# gcsc_ii.net
KiCad netlist of a schematic drawn in EAGLE
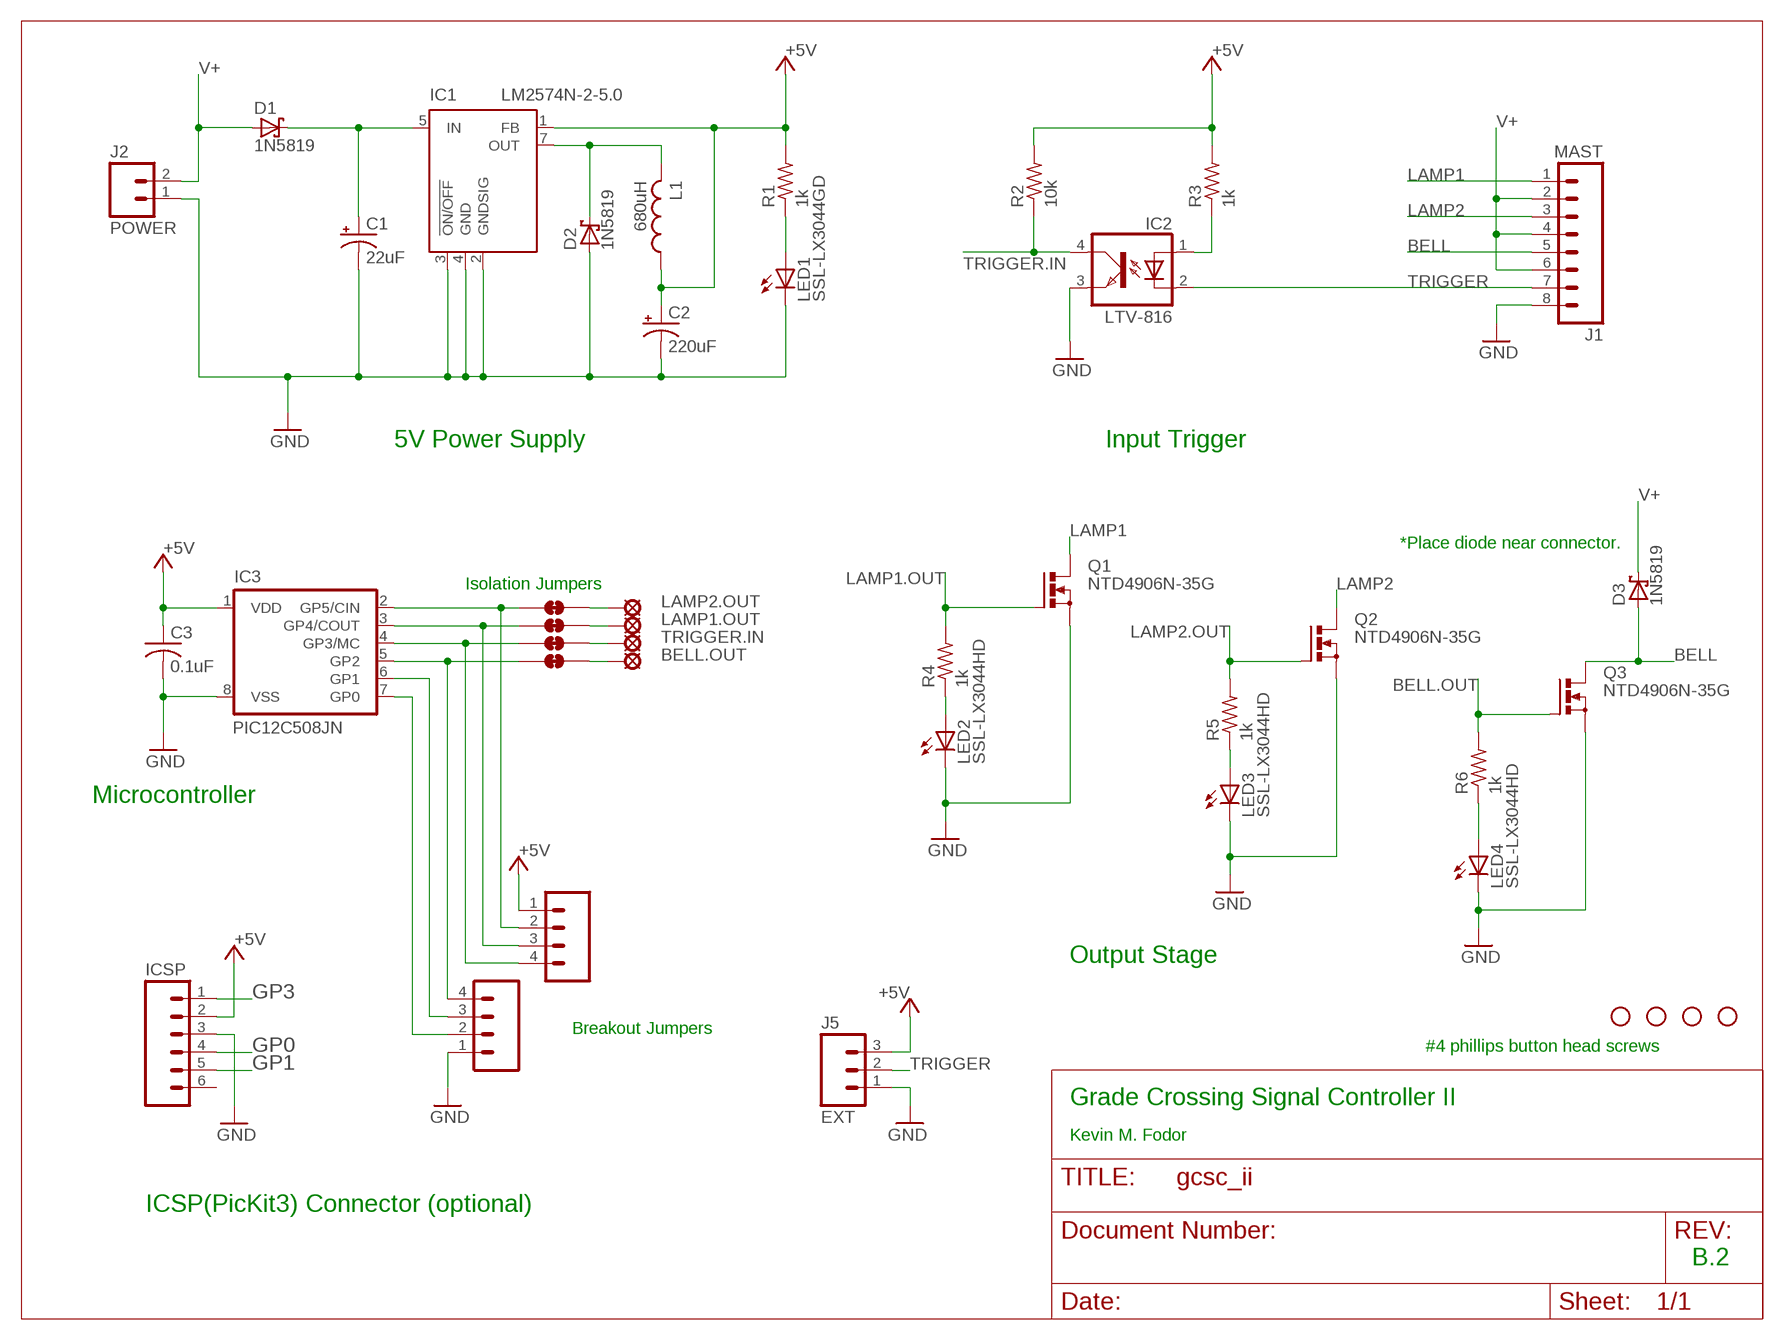
[diagram p0: schematic, sheet 1]

(export (version "E")
  (design (tool "Eeschema 10.0.6"))
  (components
    (comp (ref "BELL.OUT")
      (value "BELL")
      (footprint "eagle-import:LSP10")
      (fields (field (name "PARTNO") "22-28-4012"))
      (libsource (lib "eagle-import") (part "LSP10"))
    )
    (comp (ref "C1")
      (value "22uF")
      (footprint "eagle-import:E2-5")
      (fields (field (name "PARTNO") "EEU-FR1H220"))
      (libsource (lib "eagle-import") (part "CPOL-USFR-5"))
    )
    (comp (ref "C2")
      (value "220uF")
      (footprint "eagle-import:E2,5-6,3")
      (fields (field (name "PARTNO") "EEU-FR1C221"))
      (libsource (lib "eagle-import") (part "CPOL-USFR-6,3"))
    )
    (comp (ref "C3")
      (value "0.1uF")
      (footprint "eagle-import:C025-024X044")
      (fields (field (name "PARTNO") "21RZ310-RC"))
      (libsource (lib "eagle-import") (part "C-USC025-024X044"))
    )
    (comp (ref "D1")
      (value "1N5819")
      (footprint "eagle-import:DO41-10")
      (libsource (lib "eagle-import") (part "SCHOTTKY-DIODEDO41"))
    )
    (comp (ref "D2")
      (value "1N5819")
      (footprint "eagle-import:DO41-10")
      (libsource (lib "eagle-import") (part "SCHOTTKY-DIODEDO41"))
    )
    (comp (ref "D3")
      (value "1N5819")
      (footprint "eagle-import:DO41-10")
      (libsource (lib "eagle-import") (part "SCHOTTKY-DIODEDO41"))
    )
    (comp (ref "GP2")
      (value "GP2")
      (footprint "eagle-import:SJ_2S-TRACE")
      (libsource (lib "eagle-import") (part "SJ_CLOSED"))
    )
    (comp (ref "GP3")
      (value "GP3")
      (footprint "eagle-import:SJ_2S-TRACE")
      (libsource (lib "eagle-import") (part "SJ_CLOSED"))
    )
    (comp (ref "GP4")
      (value "GP4")
      (footprint "eagle-import:SJ_2S-TRACE")
      (libsource (lib "eagle-import") (part "SJ_CLOSED"))
    )
    (comp (ref "GP5")
      (value "GP5")
      (footprint "eagle-import:SJ_2S-TRACE")
      (libsource (lib "eagle-import") (part "SJ_CLOSED"))
    )
    (comp (ref "IC1")
      (value "LM2574N-2-5.0")
      (footprint "eagle-import:DIL8")
      (fields (field (name "PARTNO") "LM2574N-5G"))
      (libsource (lib "eagle-import") (part "LM2574?-N-25.0"))
    )
    (comp (ref "IC2")
      (value "LTV-816")
      (footprint "eagle-import:DIL04")
      (libsource (lib "eagle-import") (part "LTV816"))
    )
    (comp (ref "IC3")
      (value "PIC12C508JN")
      (footprint "eagle-import:DIL8")
      (fields
        (field (name "MF") "MICROCHIP")
        (field (name "MPN") "PIC12C508-04/P")
        (field (name "MPN_1") "PIC12C508-04/P")
        (field (name "OC_FARNELL") "9758771")
        (field (name "OC_NEWARK") "60K6710")
        (field (name "PARTNO") "PIC12F508-I/P")
      )
      (libsource (lib "eagle-import") (part "PIC12C?JN508"))
    )
    (comp (ref "ICSP")
      (value "PIC_ICSP_RA")
      (footprint "eagle-import:PIC_ICSP")
      (fields (field (name "PARTNO") "68016-106HLF"))
      (libsource (lib "eagle-import") (part "PIC_ICSP_RA"))
    )
    (comp (ref "J1")
      (value "MAST")
      (footprint "eagle-import:KK-156-8-RA")
      (fields (field (name "PARTNO") "26-60-5080"))
      (libsource (lib "eagle-import") (part "KK-156-8-RA"))
    )
    (comp (ref "J2")
      (value "POWER")
      (footprint "eagle-import:KK-156-2-RA")
      (fields (field (name "PARTNO") "26-60-5020"))
      (libsource (lib "eagle-import") (part "KK-156-2RA"))
    )
    (comp (ref "J3")
      (value "IC3_1-4")
      (footprint "eagle-import:1X04_LOCK")
      (fields (field (name "PARTNO") "22-28-4042"))
      (libsource (lib "eagle-import") (part "M04LOCK"))
    )
    (comp (ref "J4")
      (value "IC3_5-8")
      (footprint "eagle-import:1X04_LOCK")
      (fields (field (name "PARTNO") "22-28-4042"))
      (libsource (lib "eagle-import") (part "M04LOCK"))
    )
    (comp (ref "J5")
      (value "EXT")
      (footprint "eagle-import:MOLEX-1X3_LOCK")
      (fields (field (name "PARTNO") "22-27-2031"))
      (libsource (lib "eagle-import") (part "M03POLAR_LOCK"))
    )
    (comp (ref "L1")
      (value "680uH")
      (footprint "eagle-import:RLB0608")
      (fields (field (name "PARTNO") "RLB0608-681KL"))
      (libsource (lib "eagle-import") (part "RLB0608"))
    )
    (comp (ref "LAMP1.OUT")
      (value "LAMP1")
      (footprint "eagle-import:LSP10")
      (fields (field (name "PARTNO") "22-28-4012"))
      (libsource (lib "eagle-import") (part "LSP10"))
    )
    (comp (ref "LAMP2.OUT")
      (value "LAMP2")
      (footprint "eagle-import:LSP10")
      (fields (field (name "PARTNO") "22-28-4012"))
      (libsource (lib "eagle-import") (part "LSP10"))
    )
    (comp (ref "LED1")
      (value "SSL-LX3044GD")
      (footprint "eagle-import:LED3MM")
      (libsource (lib "eagle-import") (part "LED3MM"))
    )
    (comp (ref "LED2")
      (value "SSL-LX3044HD")
      (footprint "eagle-import:LED3MM")
      (libsource (lib "eagle-import") (part "LED3MM"))
    )
    (comp (ref "LED3")
      (value "SSL-LX3044HD")
      (footprint "eagle-import:LED3MM")
      (libsource (lib "eagle-import") (part "LED3MM"))
    )
    (comp (ref "LED4")
      (value "SSL-LX3044HD")
      (footprint "eagle-import:LED3MM")
      (libsource (lib "eagle-import") (part "LED3MM"))
    )
    (comp (ref "Q1")
      (value "NTD4906N-35G")
      (footprint "eagle-import:I-PAK_STRAIGHT_LEAD")
      (libsource (lib "eagle-import") (part "NTD4906N"))
    )
    (comp (ref "Q2")
      (value "NTD4906N-35G")
      (footprint "eagle-import:I-PAK_STRAIGHT_LEAD")
      (libsource (lib "eagle-import") (part "NTD4906N"))
    )
    (comp (ref "Q3")
      (value "NTD4906N-35G")
      (footprint "eagle-import:I-PAK_STRAIGHT_LEAD")
      (libsource (lib "eagle-import") (part "NTD4906N"))
    )
    (comp (ref "R1")
      (value "1k")
      (footprint "eagle-import:0207_10")
      (fields (field (name "PARTNO") "299-1K-RC"))
      (libsource (lib "eagle-import") (part "R-US0207/10"))
    )
    (comp (ref "R2")
      (value "10k")
      (footprint "eagle-import:0207_10")
      (fields (field (name "PARTNO") "299-10K-RC"))
      (libsource (lib "eagle-import") (part "R-US0207/10"))
    )
    (comp (ref "R3")
      (value "1k")
      (footprint "eagle-import:0207_10")
      (fields (field (name "PARTNO") "299-1K-RC"))
      (libsource (lib "eagle-import") (part "R-US0207/10"))
    )
    (comp (ref "R4")
      (value "1k")
      (footprint "eagle-import:0207_10")
      (fields (field (name "PARTNO") "299-1K-RC"))
      (libsource (lib "eagle-import") (part "R-US0207/10"))
    )
    (comp (ref "R5")
      (value "1k")
      (footprint "eagle-import:0207_10")
      (fields (field (name "PARTNO") "299-1K-RC"))
      (libsource (lib "eagle-import") (part "R-US0207/10"))
    )
    (comp (ref "R6")
      (value "1k")
      (footprint "eagle-import:0207_10")
      (fields (field (name "PARTNO") "299-1K-RC"))
      (libsource (lib "eagle-import") (part "R-US0207/10"))
    )
    (comp (ref "TRIGGER.IN")
      (value "TRIGGER")
      (footprint "eagle-import:LSP10")
      (fields (field (name "PARTNO") "22-28-4012"))
      (libsource (lib "eagle-import") (part "LSP10"))
    )
    (comp (ref "U$1")
      (value "STAND-OFF")
      (footprint "eagle-import:STAND-OFF")
      (libsource (lib "eagle-import") (part "STAND-OFF"))
    )
    (comp (ref "U$2")
      (value "STAND-OFF")
      (footprint "eagle-import:STAND-OFF")
      (libsource (lib "eagle-import") (part "STAND-OFF"))
    )
    (comp (ref "U$3")
      (value "STAND-OFF")
      (footprint "eagle-import:STAND-OFF")
      (libsource (lib "eagle-import") (part "STAND-OFF"))
    )
    (comp (ref "U$4")
      (value "STAND-OFF")
      (footprint "eagle-import:STAND-OFF")
      (libsource (lib "eagle-import") (part "STAND-OFF"))
    )
  )
  (nets
    (net (code "1") (name "+5V") (class "Default")
      (node (ref "C2") (pin "+") (pinfunction "+_+") (pintype "passive"))
      (node (ref "C3") (pin "1") (pinfunction "1_1") (pintype "passive"))
      (node (ref "IC1") (pin "1") (pinfunction "FB_1") (pintype "input"))
      (node (ref "IC3") (pin "1") (pinfunction "VDD_1") (pintype "power_in"))
      (node (ref "ICSP") (pin "2") (pinfunction "VDD_2") (pintype "power_in"))
      (node (ref "J3") (pin "1") (pinfunction "1_1") (pintype "passive"))
      (node (ref "J5") (pin "3") (pinfunction "3_3") (pintype "passive"))
      (node (ref "L1") (pin "1") (pinfunction "1_1") (pintype "passive"))
      (node (ref "R1") (pin "2") (pinfunction "2_2") (pintype "passive"))
      (node (ref "R2") (pin "2") (pinfunction "2_2") (pintype "passive"))
      (node (ref "R3") (pin "2") (pinfunction "2_2") (pintype "passive"))
    )
    (net (code "2") (name "/BELL") (class "Default")
      (node (ref "D3") (pin "A") (pinfunction "A_A") (pintype "passive"))
      (node (ref "J1") (pin "5") (pinfunction "5_5") (pintype "passive"))
      (node (ref "Q3") (pin "2") (pinfunction "D_2") (pintype "passive"))
    )
    (net (code "3") (name "/BELL.OUT") (class "Default")
      (node (ref "BELL.OUT") (pin "MP") (pinfunction "MP_MP") (pintype "passive"))
      (node (ref "GP2") (pin "2") (pinfunction "2_2") (pintype "passive"))
      (node (ref "Q3") (pin "1") (pinfunction "G_1") (pintype "passive"))
      (node (ref "R6") (pin "2") (pinfunction "2_2") (pintype "passive"))
    )
    (net (code "4") (name "/GP0") (class "Default")
      (node (ref "IC3") (pin "7") (pinfunction "GP0_7") (pintype "bidirectional"))
      (node (ref "ICSP") (pin "4") (pinfunction "ICSPDAT_4") (pintype "passive"))
      (node (ref "J4") (pin "2") (pinfunction "2_2") (pintype "passive"))
    )
    (net (code "5") (name "/GP1") (class "Default")
      (node (ref "IC3") (pin "6") (pinfunction "GP1_6") (pintype "bidirectional"))
      (node (ref "ICSP") (pin "5") (pinfunction "ICSPCLK_5") (pintype "passive"))
      (node (ref "J4") (pin "3") (pinfunction "3_3") (pintype "passive"))
    )
    (net (code "6") (name "/GP3") (class "Default")
      (node (ref "GP3") (pin "1") (pinfunction "1_1") (pintype "passive"))
      (node (ref "IC3") (pin "4") (pinfunction "GP3/MC_4") (pintype "input"))
      (node (ref "ICSP") (pin "1") (pinfunction "~{MCLR}_1") (pintype "passive"))
      (node (ref "J3") (pin "4") (pinfunction "4_4") (pintype "passive"))
    )
    (net (code "7") (name "/LAMP1") (class "Default")
      (node (ref "J1") (pin "1") (pinfunction "1_1") (pintype "passive"))
      (node (ref "Q1") (pin "2") (pinfunction "D_2") (pintype "passive"))
    )
    (net (code "8") (name "/LAMP1.OUT") (class "Default")
      (node (ref "GP4") (pin "2") (pinfunction "2_2") (pintype "passive"))
      (node (ref "LAMP1.OUT") (pin "MP") (pinfunction "MP_MP") (pintype "passive"))
      (node (ref "Q1") (pin "1") (pinfunction "G_1") (pintype "passive"))
      (node (ref "R4") (pin "2") (pinfunction "2_2") (pintype "passive"))
    )
    (net (code "9") (name "/LAMP2") (class "Default")
      (node (ref "J1") (pin "3") (pinfunction "3_3") (pintype "passive"))
      (node (ref "Q2") (pin "2") (pinfunction "D_2") (pintype "passive"))
    )
    (net (code "10") (name "/LAMP2.OUT") (class "Default")
      (node (ref "GP5") (pin "2") (pinfunction "2_2") (pintype "passive"))
      (node (ref "LAMP2.OUT") (pin "MP") (pinfunction "MP_MP") (pintype "passive"))
      (node (ref "Q2") (pin "1") (pinfunction "G_1") (pintype "passive"))
      (node (ref "R5") (pin "2") (pinfunction "2_2") (pintype "passive"))
    )
    (net (code "11") (name "/TRIGGER") (class "Default")
      (node (ref "IC2") (pin "2") (pinfunction "C_2") (pintype "passive"))
      (node (ref "J1") (pin "7") (pinfunction "7_7") (pintype "passive"))
      (node (ref "J5") (pin "2") (pinfunction "2_2") (pintype "passive"))
    )
    (net (code "12") (name "/TRIGGER.IN") (class "Default")
      (node (ref "GP3") (pin "2") (pinfunction "2_2") (pintype "passive"))
      (node (ref "IC2") (pin "4") (pinfunction "COL_4") (pintype "passive"))
      (node (ref "R2") (pin "1") (pinfunction "1_1") (pintype "passive"))
      (node (ref "TRIGGER.IN") (pin "MP") (pinfunction "MP_MP") (pintype "passive"))
    )
    (net (code "13") (name "/V+") (class "Default")
      (node (ref "D1") (pin "A") (pinfunction "A_A") (pintype "passive"))
      (node (ref "D3") (pin "C") (pinfunction "C_C") (pintype "passive"))
      (node (ref "J1") (pin "2") (pinfunction "2_2") (pintype "passive"))
      (node (ref "J1") (pin "4") (pinfunction "4_4") (pintype "passive"))
      (node (ref "J1") (pin "6") (pinfunction "6_6") (pintype "passive"))
      (node (ref "J2") (pin "2") (pinfunction "2_2") (pintype "passive"))
    )
    (net (code "14") (name "GND") (class "Default")
      (node (ref "C1") (pin "-") (pinfunction "-_-") (pintype "passive"))
      (node (ref "C2") (pin "-") (pinfunction "-_-") (pintype "passive"))
      (node (ref "C3") (pin "2") (pinfunction "2_2") (pintype "passive"))
      (node (ref "D2") (pin "A") (pinfunction "A_A") (pintype "passive"))
      (node (ref "IC1") (pin "2") (pinfunction "GNDSIG_2") (pintype "input"))
      (node (ref "IC1") (pin "3") (pinfunction "~{ON/OFF}_3") (pintype "input"))
      (node (ref "IC1") (pin "4") (pinfunction "GND_4") (pintype "power_in"))
      (node (ref "IC2") (pin "3") (pinfunction "EMIT_3") (pintype "passive"))
      (node (ref "IC3") (pin "8") (pinfunction "VSS_8") (pintype "power_in"))
      (node (ref "ICSP") (pin "3") (pinfunction "VSS_3") (pintype "power_in"))
      (node (ref "J1") (pin "8") (pinfunction "8_8") (pintype "passive"))
      (node (ref "J2") (pin "1") (pinfunction "1_1") (pintype "passive"))
      (node (ref "J4") (pin "1") (pinfunction "1_1") (pintype "passive"))
      (node (ref "J5") (pin "1") (pinfunction "1_1") (pintype "passive"))
      (node (ref "LED1") (pin "K") (pinfunction "C_K") (pintype "passive"))
      (node (ref "LED2") (pin "K") (pinfunction "C_K") (pintype "passive"))
      (node (ref "LED3") (pin "K") (pinfunction "C_K") (pintype "passive"))
      (node (ref "LED4") (pin "K") (pinfunction "C_K") (pintype "passive"))
      (node (ref "Q1") (pin "3") (pinfunction "S_3") (pintype "passive"))
      (node (ref "Q2") (pin "3") (pinfunction "S_3") (pintype "passive"))
      (node (ref "Q3") (pin "3") (pinfunction "S_3") (pintype "passive"))
    )
    (net (code "15") (name "Net-(IC1-IN)") (class "Default")
      (node (ref "C1") (pin "+") (pinfunction "+_+") (pintype "passive"))
      (node (ref "D1") (pin "C") (pinfunction "C_C") (pintype "passive"))
      (node (ref "IC1") (pin "5") (pinfunction "IN_5") (pintype "input"))
    )
    (net (code "16") (name "Net-(IC1-OUT)") (class "Default")
      (node (ref "D2") (pin "C") (pinfunction "C_C") (pintype "passive"))
      (node (ref "IC1") (pin "7") (pinfunction "OUT_7") (pintype "passive"))
      (node (ref "L1") (pin "2") (pinfunction "2_2") (pintype "passive"))
    )
    (net (code "17") (name "Net-(IC2-A)") (class "Default")
      (node (ref "IC2") (pin "1") (pinfunction "A_1") (pintype "passive"))
      (node (ref "R3") (pin "1") (pinfunction "1_1") (pintype "passive"))
    )
    (net (code "18") (name "Net-(IC3-GP2)") (class "Default")
      (node (ref "GP2") (pin "1") (pinfunction "1_1") (pintype "passive"))
      (node (ref "IC3") (pin "5") (pinfunction "GP2_5") (pintype "bidirectional"))
      (node (ref "J4") (pin "4") (pinfunction "4_4") (pintype "passive"))
    )
    (net (code "19") (name "Net-(IC3-GP4{slash}COUT)") (class "Default")
      (node (ref "GP4") (pin "1") (pinfunction "1_1") (pintype "passive"))
      (node (ref "IC3") (pin "3") (pinfunction "GP4/COUT_3") (pintype "bidirectional"))
      (node (ref "J3") (pin "3") (pinfunction "3_3") (pintype "passive"))
    )
    (net (code "20") (name "Net-(IC3-GP5{slash}CIN)") (class "Default")
      (node (ref "GP5") (pin "1") (pinfunction "1_1") (pintype "passive"))
      (node (ref "IC3") (pin "2") (pinfunction "GP5/CIN_2") (pintype "bidirectional"))
      (node (ref "J3") (pin "2") (pinfunction "2_2") (pintype "passive"))
    )
    (net (code "21") (name "Net-(LED1-PadA)") (class "Default")
      (node (ref "LED1") (pin "A") (pinfunction "A_A") (pintype "passive"))
      (node (ref "R1") (pin "1") (pinfunction "1_1") (pintype "passive"))
    )
    (net (code "22") (name "Net-(LED2-PadA)") (class "Default")
      (node (ref "LED2") (pin "A") (pinfunction "A_A") (pintype "passive"))
      (node (ref "R4") (pin "1") (pinfunction "1_1") (pintype "passive"))
    )
    (net (code "23") (name "Net-(LED3-PadA)") (class "Default")
      (node (ref "LED3") (pin "A") (pinfunction "A_A") (pintype "passive"))
      (node (ref "R5") (pin "1") (pinfunction "1_1") (pintype "passive"))
    )
    (net (code "24") (name "Net-(LED4-PadA)") (class "Default")
      (node (ref "LED4") (pin "A") (pinfunction "A_A") (pintype "passive"))
      (node (ref "R6") (pin "1") (pinfunction "1_1") (pintype "passive"))
    )
    (net (code "25") (name "unconnected-(ICSP-NC-Pad6)") (class "Default")
      (node (ref "ICSP") (pin "6") (pinfunction "NC_6") (pintype "no_connect"))
    )
  )
)
